# RPi_Secure_v1_2.net
KiCad netlist of a schematic drawn in EAGLE
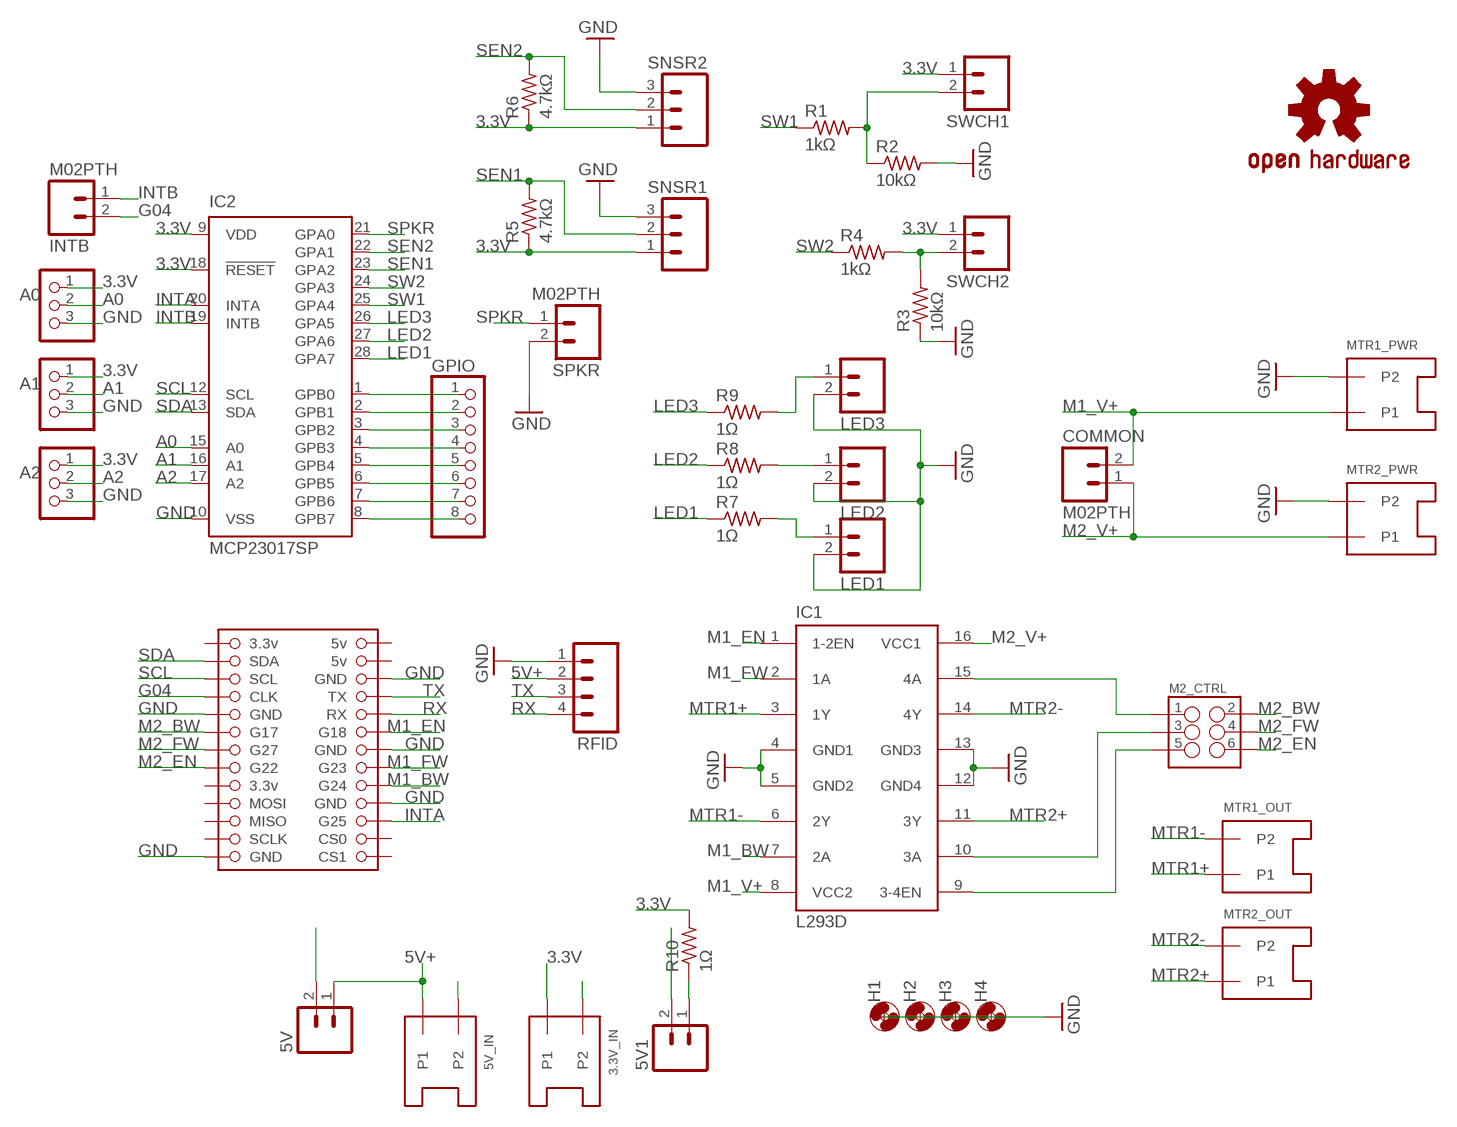
[diagram p0: schematic, sheet 1]

(export (version "E")
  (design (tool "Eeschema 10.0.6"))
  (components
    (comp (ref "3.3V_IN")
      (value "S2B-XH-AS2B-XH-A")
      (footprint "eagle-import:S2B-XH-A")
      (libsource (lib "eagle-import") (part "S2B-XH-AS2B-XH-A"))
    )
    (comp (ref "5V")
      (value "M02PTH")
      (footprint "eagle-import:1X02")
      (fields (field (name "MF") "MOLEX") (field (name "MPN") "22-28-4023"))
      (libsource (lib "eagle-import") (part "M02PTH"))
    )
    (comp (ref "5V1")
      (value "M02PTH")
      (footprint "eagle-import:1X02")
      (fields (field (name "MF") "MOLEX") (field (name "MPN") "22-28-4023"))
      (libsource (lib "eagle-import") (part "M02PTH"))
    )
    (comp (ref "5V_IN")
      (value "S2B-XH-AS2B-XH-A")
      (footprint "eagle-import:S2B-XH-A")
      (libsource (lib "eagle-import") (part "S2B-XH-AS2B-XH-A"))
    )
    (comp (ref "A0")
      (value "PINHD-1X3")
      (footprint "eagle-import:1X03")
      (fields (field (name "MPN") "22-28-4033"))
      (libsource (lib "eagle-import") (part "PINHD-1X3"))
    )
    (comp (ref "A1")
      (value "PINHD-1X3")
      (footprint "eagle-import:1X03")
      (fields (field (name "MPN") "22-28-4033"))
      (libsource (lib "eagle-import") (part "PINHD-1X3"))
    )
    (comp (ref "A2")
      (value "PINHD-1X3")
      (footprint "eagle-import:1X03")
      (fields (field (name "MPN") "22-28-4033"))
      (libsource (lib "eagle-import") (part "PINHD-1X3"))
    )
    (comp (ref "COMMON")
      (value "M02PTH")
      (footprint "eagle-import:1X02")
      (fields (field (name "MF") "MOLEX") (field (name "MPN") "22-28-4023"))
      (libsource (lib "eagle-import") (part "M02PTH"))
    )
    (comp (ref "GPIO")
      (value "PINHD-1X8")
      (footprint "eagle-import:1X08")
      (fields (field (name "MF") "MOLEX") (field (name "MPN") "22-28-4080"))
      (libsource (lib "eagle-import") (part "PINHD-1X8"))
    )
    (comp (ref "H1")
      (value "MOUNT-HOLE2.8")
      (footprint "eagle-import:2,8")
      (libsource (lib "eagle-import") (part "MOUNT-HOLE2.8"))
    )
    (comp (ref "H2")
      (value "MOUNT-HOLE2.8")
      (footprint "eagle-import:2,8")
      (libsource (lib "eagle-import") (part "MOUNT-HOLE2.8"))
    )
    (comp (ref "H3")
      (value "MOUNT-HOLE2.8")
      (footprint "eagle-import:2,8")
      (libsource (lib "eagle-import") (part "MOUNT-HOLE2.8"))
    )
    (comp (ref "H4")
      (value "MOUNT-HOLE2.8")
      (footprint "eagle-import:2,8")
      (libsource (lib "eagle-import") (part "MOUNT-HOLE2.8"))
    )
    (comp (ref "IC1")
      (value "L293D")
      (footprint "eagle-import:DIL16")
      (libsource (lib "eagle-import") (part "L293D"))
    )
    (comp (ref "IC2")
      (value "MCP23017SP")
      (footprint "eagle-import:DIL28-3")
      (fields (field (name "MF") "MICROCHIP") (field (name "MPN") "MCP23017-E/SP"))
      (libsource (lib "eagle-import") (part "MCP23017SP"))
    )
    (comp (ref "INTB")
      (value "M02PTH")
      (footprint "eagle-import:1X02")
      (fields (field (name "MF") "MOLEX") (field (name "MPN") "22-28-4023"))
      (libsource (lib "eagle-import") (part "M02PTH"))
    )
    (comp (ref "JP1")
      (value "1112RPI_EXTRA_LONG")
      (footprint "eagle-import:1112")
      (libsource (lib "eagle-import") (part "1112RPI_EXTRA_LONG"))
    )
    (comp (ref "LED1")
      (value "M02PTH")
      (footprint "eagle-import:1X02")
      (fields (field (name "MF") "MOLEX") (field (name "MPN") "22-28-4023"))
      (libsource (lib "eagle-import") (part "M02PTH"))
    )
    (comp (ref "LED2")
      (value "M02PTH")
      (footprint "eagle-import:1X02")
      (fields (field (name "MF") "MOLEX") (field (name "MPN") "22-28-4023"))
      (libsource (lib "eagle-import") (part "M02PTH"))
    )
    (comp (ref "LED3")
      (value "M02PTH")
      (footprint "eagle-import:1X02")
      (fields (field (name "MF") "MOLEX") (field (name "MPN") "22-28-4023"))
      (libsource (lib "eagle-import") (part "M02PTH"))
    )
    (comp (ref "LOGO2")
      (value "OSHW-LOGOM")
      (footprint "eagle-import:OSHW-LOGO-M")
      (libsource (lib "eagle-import") (part "OSHW-LOGOM"))
    )
    (comp (ref "M2_CTRL")
      (value "M03X22X3_SILK_SM")
      (footprint "eagle-import:2X3")
      (libsource (lib "eagle-import") (part "M03X22X3_SILK_SM"))
    )
    (comp (ref "MTR1_OUT")
      (value "S2B-XH-AS2B-XH-A")
      (footprint "eagle-import:S2B-XH-A")
      (libsource (lib "eagle-import") (part "S2B-XH-AS2B-XH-A"))
    )
    (comp (ref "MTR1_PWR")
      (value "S2B-XH-AS2B-XH-A")
      (footprint "eagle-import:S2B-XH-A")
      (libsource (lib "eagle-import") (part "S2B-XH-AS2B-XH-A"))
    )
    (comp (ref "MTR2_OUT")
      (value "S2B-XH-AS2B-XH-A")
      (footprint "eagle-import:S2B-XH-A")
      (libsource (lib "eagle-import") (part "S2B-XH-AS2B-XH-A"))
    )
    (comp (ref "MTR2_PWR")
      (value "S2B-XH-AS2B-XH-A")
      (footprint "eagle-import:S2B-XH-A")
      (libsource (lib "eagle-import") (part "S2B-XH-AS2B-XH-A"))
    )
    (comp (ref "R1")
      (value "1kΩ")
      (footprint "eagle-import:R0805")
      (libsource (lib "eagle-import") (part "R-US_R0805"))
    )
    (comp (ref "R2")
      (value "10kΩ")
      (footprint "eagle-import:R0805")
      (libsource (lib "eagle-import") (part "R-US_R0805"))
    )
    (comp (ref "R3")
      (value "10kΩ")
      (footprint "eagle-import:R0805")
      (libsource (lib "eagle-import") (part "R-US_R0805"))
    )
    (comp (ref "R4")
      (value "1kΩ")
      (footprint "eagle-import:R0805")
      (libsource (lib "eagle-import") (part "R-US_R0805"))
    )
    (comp (ref "R5")
      (value "4.7kΩ")
      (footprint "eagle-import:R0805")
      (libsource (lib "eagle-import") (part "R-US_R0805"))
    )
    (comp (ref "R6")
      (value "4.7kΩ")
      (footprint "eagle-import:R0805")
      (libsource (lib "eagle-import") (part "R-US_R0805"))
    )
    (comp (ref "R7")
      (value "1Ω")
      (footprint "eagle-import:R0805")
      (libsource (lib "eagle-import") (part "R-US_R0805"))
    )
    (comp (ref "R8")
      (value "1Ω")
      (footprint "eagle-import:R0805")
      (libsource (lib "eagle-import") (part "R-US_R0805"))
    )
    (comp (ref "R9")
      (value "1Ω")
      (footprint "eagle-import:R0805")
      (libsource (lib "eagle-import") (part "R-US_R0805"))
    )
    (comp (ref "R10")
      (value "1Ω")
      (footprint "eagle-import:R0805")
      (libsource (lib "eagle-import") (part "R-US_R0805"))
    )
    (comp (ref "RFID")
      (value "M04PTH")
      (footprint "eagle-import:1X04")
      (fields (field (name "MPN") "22-28-4040"))
      (libsource (lib "eagle-import") (part "M04PTH"))
    )
    (comp (ref "SNSR1")
      (value "M03PTH")
      (footprint "eagle-import:1X03")
      (fields (field (name "MPN") "22-28-4033"))
      (libsource (lib "eagle-import") (part "M03PTH"))
    )
    (comp (ref "SNSR2")
      (value "M03PTH")
      (footprint "eagle-import:1X03")
      (fields (field (name "MPN") "22-28-4033"))
      (libsource (lib "eagle-import") (part "M03PTH"))
    )
    (comp (ref "SPKR")
      (value "M02PTH")
      (footprint "eagle-import:1X02")
      (fields (field (name "MF") "MOLEX") (field (name "MPN") "22-28-4023"))
      (libsource (lib "eagle-import") (part "M02PTH"))
    )
    (comp (ref "SWCH1")
      (value "M02PTH")
      (footprint "eagle-import:1X02")
      (fields (field (name "MF") "MOLEX") (field (name "MPN") "22-28-4023"))
      (libsource (lib "eagle-import") (part "M02PTH"))
    )
    (comp (ref "SWCH2")
      (value "M02PTH")
      (footprint "eagle-import:1X02")
      (fields (field (name "MF") "MOLEX") (field (name "MPN") "22-28-4023"))
      (libsource (lib "eagle-import") (part "M02PTH"))
    )
  )
  (nets
    (net (code "1") (name "/01") (class "Default")
      (node (ref "JP1") (pin "01") (pinfunction "01_01") (pintype "power_in"))
    )
    (net (code "2") (name "/02") (class "Default")
      (node (ref "JP1") (pin "02") (pinfunction "02_02") (pintype "power_in"))
    )
    (net (code "3") (name "/3.3V") (class "Default")
      (node (ref "3.3V_IN") (pin "P1") (pinfunction "P1_P1") (pintype "bidirectional"))
      (node (ref "A0") (pin "1") (pinfunction "1_1") (pintype "passive"))
      (node (ref "A1") (pin "1") (pinfunction "1_1") (pintype "passive"))
      (node (ref "A2") (pin "1") (pinfunction "1_1") (pintype "passive"))
      (node (ref "IC2") (pin "18") (pinfunction "~{RESET}_18") (pintype "input"))
      (node (ref "IC2") (pin "9") (pinfunction "VDD_9") (pintype "power_in"))
      (node (ref "R10") (pin "2") (pinfunction "2_2") (pintype "passive"))
      (node (ref "R5") (pin "1") (pinfunction "1_1") (pintype "passive"))
      (node (ref "R6") (pin "1") (pinfunction "1_1") (pintype "passive"))
      (node (ref "SNSR1") (pin "1") (pinfunction "1_1") (pintype "passive"))
      (node (ref "SNSR2") (pin "1") (pinfunction "1_1") (pintype "passive"))
      (node (ref "SWCH1") (pin "1") (pinfunction "1_1") (pintype "passive"))
      (node (ref "SWCH2") (pin "1") (pinfunction "1_1") (pintype "passive"))
    )
    (net (code "4") (name "/04") (class "Default")
      (node (ref "JP1") (pin "04") (pinfunction "04_04") (pintype "power_in"))
    )
    (net (code "5") (name "/5V+") (class "Default")
      (node (ref "5V") (pin "1") (pinfunction "1_1") (pintype "passive"))
      (node (ref "5V_IN") (pin "P1") (pinfunction "P1_P1") (pintype "bidirectional"))
      (node (ref "RFID") (pin "2") (pinfunction "2_2") (pintype "passive"))
    )
    (net (code "6") (name "/17") (class "Default")
      (node (ref "JP1") (pin "17") (pinfunction "17_17") (pintype "power_in"))
    )
    (net (code "7") (name "/A0") (class "Default")
      (node (ref "A0") (pin "2") (pinfunction "2_2") (pintype "passive"))
      (node (ref "IC2") (pin "15") (pinfunction "A0_15") (pintype "input"))
    )
    (net (code "8") (name "/A1") (class "Default")
      (node (ref "A1") (pin "2") (pinfunction "2_2") (pintype "passive"))
      (node (ref "IC2") (pin "16") (pinfunction "A1_16") (pintype "input"))
    )
    (net (code "9") (name "/A2") (class "Default")
      (node (ref "A2") (pin "2") (pinfunction "2_2") (pintype "passive"))
      (node (ref "IC2") (pin "17") (pinfunction "A2_17") (pintype "input"))
    )
    (net (code "10") (name "/G04") (class "Default")
      (node (ref "INTB") (pin "2") (pinfunction "2_2") (pintype "passive"))
      (node (ref "JP1") (pin "07") (pinfunction "07_07") (pintype "bidirectional"))
    )
    (net (code "11") (name "/INTA") (class "Default")
      (node (ref "IC2") (pin "20") (pinfunction "INTA_20") (pintype "output"))
      (node (ref "JP1") (pin "22") (pinfunction "22_22") (pintype "bidirectional"))
    )
    (net (code "12") (name "/INTB") (class "Default")
      (node (ref "IC2") (pin "19") (pinfunction "INTB_19") (pintype "output"))
      (node (ref "INTB") (pin "1") (pinfunction "1_1") (pintype "passive"))
    )
    (net (code "13") (name "/LED1") (class "Default")
      (node (ref "IC2") (pin "28") (pinfunction "GPA7_28") (pintype "bidirectional"))
      (node (ref "R7") (pin "1") (pinfunction "1_1") (pintype "passive"))
    )
    (net (code "14") (name "/LED2") (class "Default")
      (node (ref "IC2") (pin "27") (pinfunction "GPA6_27") (pintype "bidirectional"))
      (node (ref "R8") (pin "1") (pinfunction "1_1") (pintype "passive"))
    )
    (net (code "15") (name "/LED3") (class "Default")
      (node (ref "IC2") (pin "26") (pinfunction "GPA5_26") (pintype "bidirectional"))
      (node (ref "R9") (pin "1") (pinfunction "1_1") (pintype "passive"))
    )
    (net (code "16") (name "/M1_BW") (class "Default")
      (node (ref "IC1") (pin "7") (pinfunction "2A_7") (pintype "input"))
      (node (ref "JP1") (pin "18") (pinfunction "18_18") (pintype "bidirectional"))
    )
    (net (code "17") (name "/M1_EN") (class "Default")
      (node (ref "IC1") (pin "1") (pinfunction "1-2EN_1") (pintype "input"))
      (node (ref "JP1") (pin "12") (pinfunction "12_12") (pintype "bidirectional"))
    )
    (net (code "18") (name "/M1_FW") (class "Default")
      (node (ref "IC1") (pin "2") (pinfunction "1A_2") (pintype "input"))
      (node (ref "JP1") (pin "16") (pinfunction "16_16") (pintype "bidirectional"))
    )
    (net (code "19") (name "/M1_V+") (class "Default")
      (node (ref "COMMON") (pin "2") (pinfunction "2_2") (pintype "passive"))
      (node (ref "IC1") (pin "8") (pinfunction "VCC2_8") (pintype "power_in"))
      (node (ref "MTR1_PWR") (pin "P1") (pinfunction "P1_P1") (pintype "bidirectional"))
    )
    (net (code "20") (name "/M2_BW") (class "Default")
      (node (ref "JP1") (pin "11") (pinfunction "11_11") (pintype "bidirectional"))
      (node (ref "M2_CTRL") (pin "2") (pinfunction "2_2") (pintype "bidirectional"))
    )
    (net (code "21") (name "/M2_EN") (class "Default")
      (node (ref "JP1") (pin "15") (pinfunction "15_15") (pintype "bidirectional"))
      (node (ref "M2_CTRL") (pin "6") (pinfunction "6_6") (pintype "bidirectional"))
    )
    (net (code "22") (name "/M2_FW") (class "Default")
      (node (ref "JP1") (pin "13") (pinfunction "13_13") (pintype "bidirectional"))
      (node (ref "M2_CTRL") (pin "4") (pinfunction "4_4") (pintype "bidirectional"))
    )
    (net (code "23") (name "/M2_V+") (class "Default")
      (node (ref "COMMON") (pin "1") (pinfunction "1_1") (pintype "passive"))
      (node (ref "IC1") (pin "16") (pinfunction "VCC1_16") (pintype "power_in"))
      (node (ref "MTR2_PWR") (pin "P1") (pinfunction "P1_P1") (pintype "bidirectional"))
    )
    (net (code "24") (name "/MTR1+") (class "Default")
      (node (ref "IC1") (pin "3") (pinfunction "1Y_3") (pintype "output"))
      (node (ref "MTR1_OUT") (pin "P1") (pinfunction "P1_P1") (pintype "bidirectional"))
    )
    (net (code "25") (name "/MTR1-") (class "Default")
      (node (ref "IC1") (pin "6") (pinfunction "2Y_6") (pintype "output"))
      (node (ref "MTR1_OUT") (pin "P2") (pinfunction "P2_P2") (pintype "bidirectional"))
    )
    (net (code "26") (name "/MTR2+") (class "Default")
      (node (ref "IC1") (pin "11") (pinfunction "3Y_11") (pintype "output"))
      (node (ref "MTR2_OUT") (pin "P1") (pinfunction "P1_P1") (pintype "bidirectional"))
    )
    (net (code "27") (name "/MTR2-") (class "Default")
      (node (ref "IC1") (pin "14") (pinfunction "4Y_14") (pintype "output"))
      (node (ref "MTR2_OUT") (pin "P2") (pinfunction "P2_P2") (pintype "bidirectional"))
    )
    (net (code "28") (name "/RX") (class "Default")
      (node (ref "JP1") (pin "10") (pinfunction "10_10") (pintype "bidirectional"))
      (node (ref "RFID") (pin "4") (pinfunction "4_4") (pintype "passive"))
    )
    (net (code "29") (name "/SCL") (class "Default")
      (node (ref "IC2") (pin "12") (pinfunction "SCL_12") (pintype "input"))
      (node (ref "JP1") (pin "05") (pinfunction "05_05") (pintype "bidirectional"))
    )
    (net (code "30") (name "/SDA") (class "Default")
      (node (ref "IC2") (pin "13") (pinfunction "SDA_13") (pintype "bidirectional"))
      (node (ref "JP1") (pin "03") (pinfunction "03_03") (pintype "bidirectional"))
    )
    (net (code "31") (name "/SEN1") (class "Default")
      (node (ref "IC2") (pin "23") (pinfunction "GPA2_23") (pintype "bidirectional"))
      (node (ref "R5") (pin "2") (pinfunction "2_2") (pintype "passive"))
      (node (ref "SNSR1") (pin "2") (pinfunction "2_2") (pintype "passive"))
    )
    (net (code "32") (name "/SEN2") (class "Default")
      (node (ref "IC2") (pin "22") (pinfunction "GPA1_22") (pintype "bidirectional"))
      (node (ref "R6") (pin "2") (pinfunction "2_2") (pintype "passive"))
      (node (ref "SNSR2") (pin "2") (pinfunction "2_2") (pintype "passive"))
    )
    (net (code "33") (name "/SPKR") (class "Default")
      (node (ref "IC2") (pin "21") (pinfunction "GPA0_21") (pintype "bidirectional"))
      (node (ref "SPKR") (pin "1") (pinfunction "1_1") (pintype "passive"))
    )
    (net (code "34") (name "/SW1") (class "Default")
      (node (ref "IC2") (pin "25") (pinfunction "GPA4_25") (pintype "bidirectional"))
      (node (ref "R1") (pin "1") (pinfunction "1_1") (pintype "passive"))
      (node (ref "R1") (pin "2") (pinfunction "2_2") (pintype "passive"))
      (node (ref "R2") (pin "1") (pinfunction "1_1") (pintype "passive"))
      (node (ref "SWCH1") (pin "2") (pinfunction "2_2") (pintype "passive"))
    )
    (net (code "35") (name "/SW2") (class "Default")
      (node (ref "IC2") (pin "24") (pinfunction "GPA3_24") (pintype "bidirectional"))
      (node (ref "R4") (pin "1") (pinfunction "1_1") (pintype "passive"))
    )
    (net (code "36") (name "/TX") (class "Default")
      (node (ref "JP1") (pin "08") (pinfunction "08_08") (pintype "bidirectional"))
      (node (ref "RFID") (pin "3") (pinfunction "3_3") (pintype "passive"))
    )
    (net (code "37") (name "GND") (class "Default")
      (node (ref "3.3V_IN") (pin "P2") (pinfunction "P2_P2") (pintype "bidirectional"))
      (node (ref "5V") (pin "2") (pinfunction "2_2") (pintype "passive"))
      (node (ref "5V1") (pin "2") (pinfunction "2_2") (pintype "passive"))
      (node (ref "5V_IN") (pin "P2") (pinfunction "P2_P2") (pintype "bidirectional"))
      (node (ref "A0") (pin "3") (pinfunction "3_3") (pintype "passive"))
      (node (ref "A1") (pin "3") (pinfunction "3_3") (pintype "passive"))
      (node (ref "A2") (pin "3") (pinfunction "3_3") (pintype "passive"))
      (node (ref "IC1") (pin "12") (pinfunction "GND4_12") (pintype "power_in"))
      (node (ref "IC1") (pin "13") (pinfunction "GND3_13") (pintype "power_in"))
      (node (ref "IC1") (pin "4") (pinfunction "GND1_4") (pintype "power_in"))
      (node (ref "IC1") (pin "5") (pinfunction "GND2_5") (pintype "power_in"))
      (node (ref "IC2") (pin "10") (pinfunction "VSS_10") (pintype "power_in"))
      (node (ref "JP1") (pin "06") (pinfunction "06_06") (pintype "bidirectional"))
      (node (ref "JP1") (pin "09") (pinfunction "09_09") (pintype "bidirectional"))
      (node (ref "JP1") (pin "14") (pinfunction "14_14") (pintype "bidirectional"))
      (node (ref "JP1") (pin "20") (pinfunction "20_20") (pintype "bidirectional"))
      (node (ref "JP1") (pin "25") (pinfunction "25_25") (pintype "bidirectional"))
      (node (ref "LED1") (pin "2") (pinfunction "2_2") (pintype "passive"))
      (node (ref "LED2") (pin "2") (pinfunction "2_2") (pintype "passive"))
      (node (ref "LED3") (pin "2") (pinfunction "2_2") (pintype "passive"))
      (node (ref "MTR1_PWR") (pin "P2") (pinfunction "P2_P2") (pintype "bidirectional"))
      (node (ref "MTR2_PWR") (pin "P2") (pinfunction "P2_P2") (pintype "bidirectional"))
      (node (ref "R2") (pin "2") (pinfunction "2_2") (pintype "passive"))
      (node (ref "R3") (pin "1") (pinfunction "1_1") (pintype "passive"))
      (node (ref "RFID") (pin "1") (pinfunction "1_1") (pintype "passive"))
      (node (ref "SNSR1") (pin "3") (pinfunction "3_3") (pintype "passive"))
      (node (ref "SNSR2") (pin "3") (pinfunction "3_3") (pintype "passive"))
      (node (ref "SPKR") (pin "2") (pinfunction "2_2") (pintype "passive"))
    )
    (net (code "38") (name "Net-(5V1-Pad1)") (class "Default")
      (node (ref "5V1") (pin "1") (pinfunction "1_1") (pintype "passive"))
      (node (ref "R10") (pin "1") (pinfunction "1_1") (pintype "passive"))
    )
    (net (code "39") (name "Net-(IC1-3-4EN)") (class "Default")
      (node (ref "IC1") (pin "9") (pinfunction "3-4EN_9") (pintype "input"))
      (node (ref "M2_CTRL") (pin "5") (pinfunction "5_5") (pintype "bidirectional"))
    )
    (net (code "40") (name "Net-(IC1-3A)") (class "Default")
      (node (ref "IC1") (pin "10") (pinfunction "3A_10") (pintype "input"))
      (node (ref "M2_CTRL") (pin "3") (pinfunction "3_3") (pintype "bidirectional"))
    )
    (net (code "41") (name "Net-(IC1-4A)") (class "Default")
      (node (ref "IC1") (pin "15") (pinfunction "4A_15") (pintype "input"))
      (node (ref "M2_CTRL") (pin "1") (pinfunction "1_1") (pintype "bidirectional"))
    )
    (net (code "42") (name "Net-(IC2-GPB0)") (class "Default")
      (node (ref "GPIO") (pin "1") (pinfunction "1_1") (pintype "passive"))
      (node (ref "IC2") (pin "1") (pinfunction "GPB0_1") (pintype "bidirectional"))
    )
    (net (code "43") (name "Net-(IC2-GPB1)") (class "Default")
      (node (ref "GPIO") (pin "2") (pinfunction "2_2") (pintype "passive"))
      (node (ref "IC2") (pin "2") (pinfunction "GPB1_2") (pintype "bidirectional"))
    )
    (net (code "44") (name "Net-(IC2-GPB2)") (class "Default")
      (node (ref "GPIO") (pin "3") (pinfunction "3_3") (pintype "passive"))
      (node (ref "IC2") (pin "3") (pinfunction "GPB2_3") (pintype "bidirectional"))
    )
    (net (code "45") (name "Net-(IC2-GPB3)") (class "Default")
      (node (ref "GPIO") (pin "4") (pinfunction "4_4") (pintype "passive"))
      (node (ref "IC2") (pin "4") (pinfunction "GPB3_4") (pintype "bidirectional"))
    )
    (net (code "46") (name "Net-(IC2-GPB4)") (class "Default")
      (node (ref "GPIO") (pin "5") (pinfunction "5_5") (pintype "passive"))
      (node (ref "IC2") (pin "5") (pinfunction "GPB4_5") (pintype "bidirectional"))
    )
    (net (code "47") (name "Net-(IC2-GPB5)") (class "Default")
      (node (ref "GPIO") (pin "6") (pinfunction "6_6") (pintype "passive"))
      (node (ref "IC2") (pin "6") (pinfunction "GPB5_6") (pintype "bidirectional"))
    )
    (net (code "48") (name "Net-(IC2-GPB6)") (class "Default")
      (node (ref "GPIO") (pin "7") (pinfunction "7_7") (pintype "passive"))
      (node (ref "IC2") (pin "7") (pinfunction "GPB6_7") (pintype "bidirectional"))
    )
    (net (code "49") (name "Net-(IC2-GPB7)") (class "Default")
      (node (ref "GPIO") (pin "8") (pinfunction "8_8") (pintype "passive"))
      (node (ref "IC2") (pin "8") (pinfunction "GPB7_8") (pintype "bidirectional"))
    )
    (net (code "50") (name "Net-(LED1-Pad1)") (class "Default")
      (node (ref "LED1") (pin "1") (pinfunction "1_1") (pintype "passive"))
      (node (ref "R7") (pin "2") (pinfunction "2_2") (pintype "passive"))
    )
    (net (code "51") (name "Net-(LED2-Pad1)") (class "Default")
      (node (ref "LED2") (pin "1") (pinfunction "1_1") (pintype "passive"))
      (node (ref "R8") (pin "2") (pinfunction "2_2") (pintype "passive"))
    )
    (net (code "52") (name "Net-(LED3-Pad1)") (class "Default")
      (node (ref "LED3") (pin "1") (pinfunction "1_1") (pintype "passive"))
      (node (ref "R9") (pin "2") (pinfunction "2_2") (pintype "passive"))
    )
    (net (code "53") (name "Net-(R3-Pad2)") (class "Default")
      (node (ref "R3") (pin "2") (pinfunction "2_2") (pintype "passive"))
      (node (ref "R4") (pin "2") (pinfunction "2_2") (pintype "passive"))
      (node (ref "SWCH2") (pin "2") (pinfunction "2_2") (pintype "passive"))
    )
    (net (code "54") (name "unconnected-(JP1-Pad19)") (class "Default")
      (node (ref "JP1") (pin "19") (pinfunction "19_19") (pintype "bidirectional"))
    )
    (net (code "55") (name "unconnected-(JP1-Pad21)") (class "Default")
      (node (ref "JP1") (pin "21") (pinfunction "21_21") (pintype "bidirectional"))
    )
    (net (code "56") (name "unconnected-(JP1-Pad23)") (class "Default")
      (node (ref "JP1") (pin "23") (pinfunction "23_23") (pintype "bidirectional"))
    )
    (net (code "57") (name "unconnected-(JP1-Pad24)") (class "Default")
      (node (ref "JP1") (pin "24") (pinfunction "24_24") (pintype "bidirectional"))
    )
    (net (code "58") (name "unconnected-(JP1-Pad26)") (class "Default")
      (node (ref "JP1") (pin "26") (pinfunction "26_26") (pintype "bidirectional"))
    )
  )
)
